# octanis_eps_compact.net
KiCad netlist of a schematic drawn in EAGLE
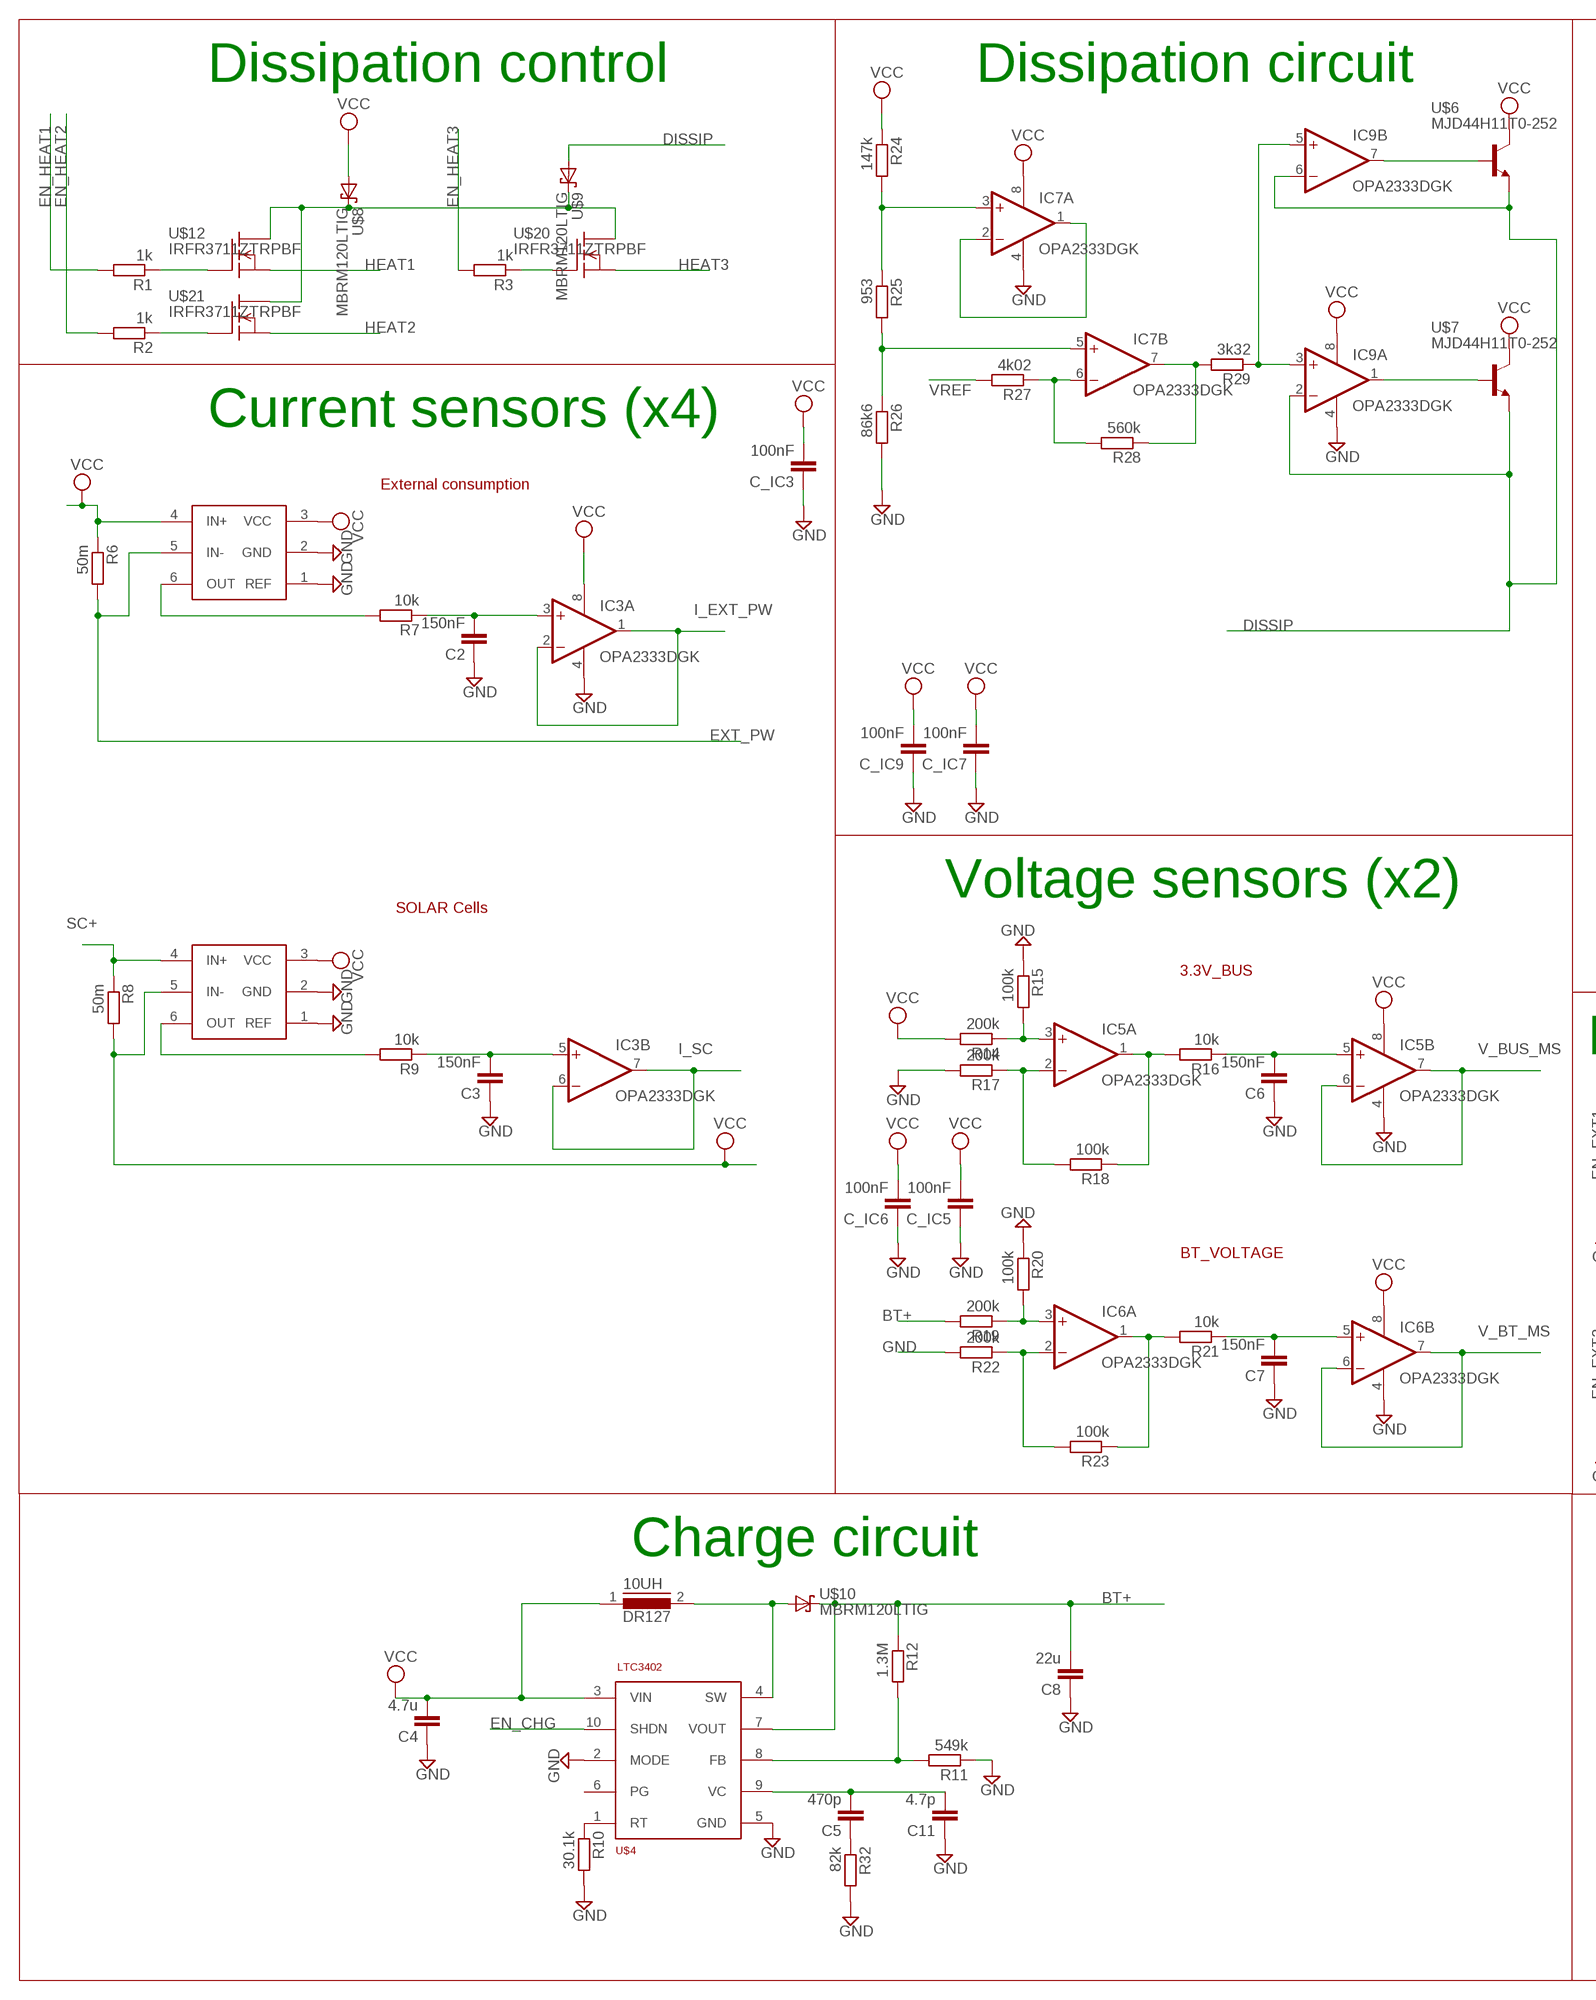
[diagram p0: schematic, sheet 1, part 1 of 2]
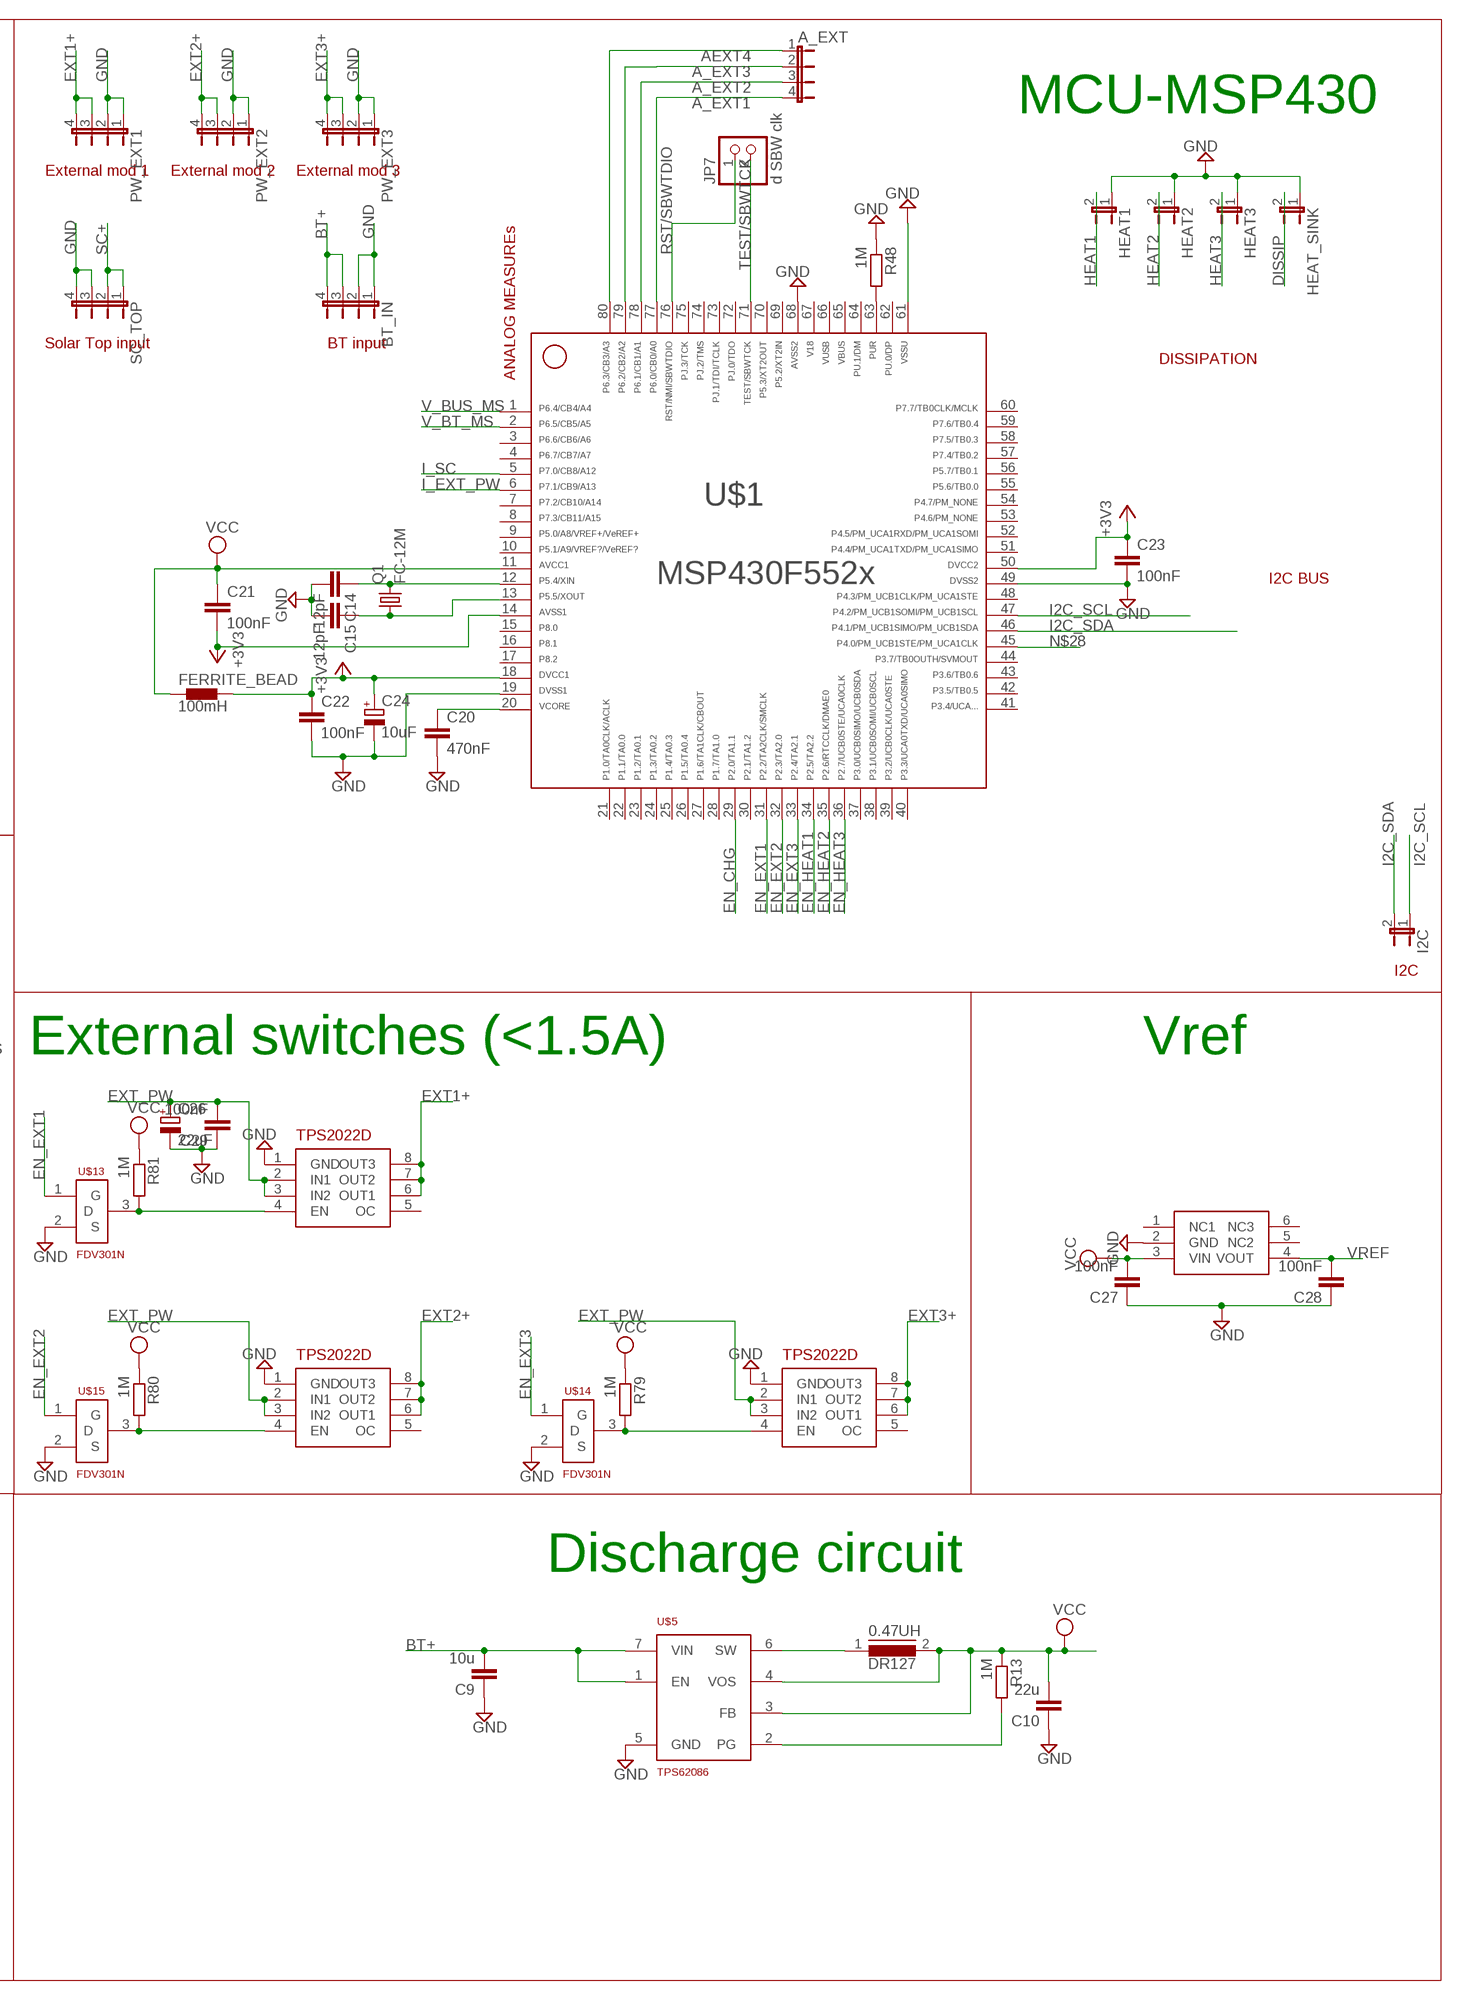
[diagram p1: schematic, sheet 1, part 2 of 2]

(export (version "E")
  (design (tool "Eeschema 10.0.6"))
  (components
    (comp (ref "0.47UH")
      (value "DR127")
      (footprint "eagle-import:DR127")
      (libsource (lib "eagle-import") (part "DR127"))
    )
    (comp (ref "10UH")
      (value "DR127")
      (footprint "eagle-import:DR127")
      (libsource (lib "eagle-import") (part "DR127"))
    )
    (comp (ref "A_EXT")
      (value "JP4E")
      (footprint "eagle-import:JP4")
      (libsource (lib "eagle-import") (part "JP4E"))
    )
    (comp (ref "BT_IN")
      (value "JP4E")
      (footprint "eagle-import:JP4")
      (libsource (lib "eagle-import") (part "JP4E"))
    )
    (comp (ref "C2")
      (value "150nF")
      (footprint "eagle-import:C0603")
      (libsource (lib "eagle-import") (part "C-EUC0603"))
    )
    (comp (ref "C3")
      (value "150nF")
      (footprint "eagle-import:C0603")
      (libsource (lib "eagle-import") (part "C-EUC0603"))
    )
    (comp (ref "C4")
      (value "4.7u")
      (footprint "eagle-import:C0603")
      (libsource (lib "eagle-import") (part "C-EUC0603"))
    )
    (comp (ref "C5")
      (value "470p")
      (footprint "eagle-import:C0603")
      (libsource (lib "eagle-import") (part "C-EUC0603"))
    )
    (comp (ref "C6")
      (value "150nF")
      (footprint "eagle-import:C0603")
      (libsource (lib "eagle-import") (part "C-EUC0603"))
    )
    (comp (ref "C7")
      (value "150nF")
      (footprint "eagle-import:C0603")
      (libsource (lib "eagle-import") (part "C-EUC0603"))
    )
    (comp (ref "C8")
      (value "22u")
      (footprint "eagle-import:C0603")
      (libsource (lib "eagle-import") (part "C-EUC0603"))
    )
    (comp (ref "C9")
      (value "10u")
      (footprint "eagle-import:C0603")
      (libsource (lib "eagle-import") (part "C-EUC0603"))
    )
    (comp (ref "C10")
      (value "22u")
      (footprint "eagle-import:C0603")
      (libsource (lib "eagle-import") (part "C-EUC0603"))
    )
    (comp (ref "C11")
      (value "4.7p")
      (footprint "eagle-import:C0603")
      (libsource (lib "eagle-import") (part "C-EUC0603"))
    )
    (comp (ref "C14")
      (value "12pF")
      (footprint "eagle-import:C0603")
      (libsource (lib "eagle-import") (part "C-EUC0603"))
    )
    (comp (ref "C15")
      (value "12pF")
      (footprint "eagle-import:C0603")
      (libsource (lib "eagle-import") (part "C-EUC0603"))
    )
    (comp (ref "C20")
      (value "470nF")
      (footprint "eagle-import:C0603")
      (libsource (lib "eagle-import") (part "C-EUC0603"))
    )
    (comp (ref "C21")
      (value "100nF")
      (footprint "eagle-import:C0603")
      (libsource (lib "eagle-import") (part "C-EUC0603"))
    )
    (comp (ref "C22")
      (value "100nF")
      (footprint "eagle-import:C0603")
      (libsource (lib "eagle-import") (part "C-EUC0603"))
    )
    (comp (ref "C23")
      (value "100nF")
      (footprint "eagle-import:C0603")
      (libsource (lib "eagle-import") (part "C-EUC0603"))
    )
    (comp (ref "C24")
      (value "10uF")
      (footprint "eagle-import:A_3216-18R")
      (libsource (lib "eagle-import") (part "CPOL-EUA/3216-18R"))
    )
    (comp (ref "C26")
      (value "22uF")
      (footprint "eagle-import:A_3216-18R")
      (libsource (lib "eagle-import") (part "CPOL-EUA/3216-18R"))
    )
    (comp (ref "C27")
      (value "100nF")
      (footprint "eagle-import:C0603")
      (libsource (lib "eagle-import") (part "C-EUC0603"))
    )
    (comp (ref "C28")
      (value "100nF")
      (footprint "eagle-import:C0603")
      (libsource (lib "eagle-import") (part "C-EUC0603"))
    )
    (comp (ref "C29")
      (value "100nF")
      (footprint "eagle-import:C0603")
      (libsource (lib "eagle-import") (part "C-EUC0603"))
    )
    (comp (ref "C_IC3")
      (value "100nF")
      (footprint "eagle-import:C0603")
      (libsource (lib "eagle-import") (part "C-EUC0603"))
    )
    (comp (ref "C_IC5")
      (value "100nF")
      (footprint "eagle-import:C0603")
      (libsource (lib "eagle-import") (part "C-EUC0603"))
    )
    (comp (ref "C_IC6")
      (value "100nF")
      (footprint "eagle-import:C0603")
      (libsource (lib "eagle-import") (part "C-EUC0603"))
    )
    (comp (ref "C_IC7")
      (value "100nF")
      (footprint "eagle-import:C0603")
      (libsource (lib "eagle-import") (part "C-EUC0603"))
    )
    (comp (ref "C_IC9")
      (value "100nF")
      (footprint "eagle-import:C0603")
      (libsource (lib "eagle-import") (part "C-EUC0603"))
    )
    (comp (ref "FERRITE_BEAD")
      (value "100mH")
      (footprint "eagle-import:0402")
      (libsource (lib "eagle-import") (part "BLM15HD601SN1"))
    )
    (comp (ref "HEAT1")
      (value "JP1E")
      (footprint "eagle-import:JP1")
      (libsource (lib "eagle-import") (part "JP1E"))
    )
    (comp (ref "HEAT2")
      (value "JP1E")
      (footprint "eagle-import:JP1")
      (libsource (lib "eagle-import") (part "JP1E"))
    )
    (comp (ref "HEAT3")
      (value "JP1E")
      (footprint "eagle-import:JP1")
      (libsource (lib "eagle-import") (part "JP1E"))
    )
    (comp (ref "HEAT_SINK")
      (value "JP1E")
      (footprint "eagle-import:JP1")
      (libsource (lib "eagle-import") (part "JP1E"))
    )
    (comp (ref "I2C")
      (value "JP1E")
      (footprint "eagle-import:JP1")
      (libsource (lib "eagle-import") (part "JP1E"))
    )
    (comp (ref "IC3")
      (value "OPA2333DGK")
      (footprint "eagle-import:MSOP08")
      (libsource (lib "eagle-import") (part "OPA2333DGK"))
    )
    (comp (ref "IC5")
      (value "OPA2333DGK")
      (footprint "eagle-import:MSOP08")
      (libsource (lib "eagle-import") (part "OPA2333DGK"))
    )
    (comp (ref "IC6")
      (value "OPA2333DGK")
      (footprint "eagle-import:MSOP08")
      (libsource (lib "eagle-import") (part "OPA2333DGK"))
    )
    (comp (ref "IC7")
      (value "OPA2333DGK")
      (footprint "eagle-import:MSOP08")
      (libsource (lib "eagle-import") (part "OPA2333DGK"))
    )
    (comp (ref "IC9")
      (value "OPA2333DGK")
      (footprint "eagle-import:MSOP08")
      (libsource (lib "eagle-import") (part "OPA2333DGK"))
    )
    (comp (ref "JP7")
      (value "d SBW clk")
      (footprint "eagle-import:1X02")
      (libsource (lib "eagle-import") (part "PINHD-1X2"))
    )
    (comp (ref "PW_EXT1")
      (value "JP4E")
      (footprint "eagle-import:JP4")
      (libsource (lib "eagle-import") (part "JP4E"))
    )
    (comp (ref "PW_EXT2")
      (value "JP4E")
      (footprint "eagle-import:JP4")
      (libsource (lib "eagle-import") (part "JP4E"))
    )
    (comp (ref "PW_EXT3")
      (value "JP4E")
      (footprint "eagle-import:JP4")
      (libsource (lib "eagle-import") (part "JP4E"))
    )
    (comp (ref "Q1")
      (value "FC-12M")
      (footprint "eagle-import:FC-12M")
      (libsource (lib "eagle-import") (part "FC-12M"))
    )
    (comp (ref "R1")
      (value "1k")
      (footprint "eagle-import:R0603")
      (libsource (lib "eagle-import") (part "R-EU_R0603"))
    )
    (comp (ref "R2")
      (value "1k")
      (footprint "eagle-import:R0603")
      (libsource (lib "eagle-import") (part "R-EU_R0603"))
    )
    (comp (ref "R3")
      (value "1k")
      (footprint "eagle-import:R0603")
      (libsource (lib "eagle-import") (part "R-EU_R0603"))
    )
    (comp (ref "R6")
      (value "50m")
      (footprint "eagle-import:R1206")
      (libsource (lib "eagle-import") (part "R-EU_R1206"))
    )
    (comp (ref "R7")
      (value "10k")
      (footprint "eagle-import:R0603")
      (libsource (lib "eagle-import") (part "R-EU_R0603"))
    )
    (comp (ref "R8")
      (value "50m")
      (footprint "eagle-import:R1206")
      (libsource (lib "eagle-import") (part "R-EU_R1206"))
    )
    (comp (ref "R9")
      (value "10k")
      (footprint "eagle-import:R0603")
      (libsource (lib "eagle-import") (part "R-EU_R0603"))
    )
    (comp (ref "R10")
      (value "30.1k")
      (footprint "eagle-import:R0603")
      (libsource (lib "eagle-import") (part "R-EU_R0603"))
    )
    (comp (ref "R11")
      (value "549k")
      (footprint "eagle-import:R0603")
      (libsource (lib "eagle-import") (part "R-EU_R0603"))
    )
    (comp (ref "R12")
      (value "1.3M")
      (footprint "eagle-import:R0603")
      (libsource (lib "eagle-import") (part "R-EU_R0603"))
    )
    (comp (ref "R13")
      (value "1M")
      (footprint "eagle-import:R0603")
      (libsource (lib "eagle-import") (part "R-EU_R0603"))
    )
    (comp (ref "R14")
      (value "200k")
      (footprint "eagle-import:R0603")
      (libsource (lib "eagle-import") (part "R-EU_R0603"))
    )
    (comp (ref "R15")
      (value "100k")
      (footprint "eagle-import:R0603")
      (libsource (lib "eagle-import") (part "R-EU_R0603"))
    )
    (comp (ref "R16")
      (value "10k")
      (footprint "eagle-import:R0603")
      (libsource (lib "eagle-import") (part "R-EU_R0603"))
    )
    (comp (ref "R17")
      (value "200k")
      (footprint "eagle-import:R0603")
      (libsource (lib "eagle-import") (part "R-EU_R0603"))
    )
    (comp (ref "R18")
      (value "100k")
      (footprint "eagle-import:R0603")
      (libsource (lib "eagle-import") (part "R-EU_R0603"))
    )
    (comp (ref "R19")
      (value "200k")
      (footprint "eagle-import:R0603")
      (libsource (lib "eagle-import") (part "R-EU_R0603"))
    )
    (comp (ref "R20")
      (value "100k")
      (footprint "eagle-import:R0603")
      (libsource (lib "eagle-import") (part "R-EU_R0603"))
    )
    (comp (ref "R21")
      (value "10k")
      (footprint "eagle-import:R0603")
      (libsource (lib "eagle-import") (part "R-EU_R0603"))
    )
    (comp (ref "R22")
      (value "200k")
      (footprint "eagle-import:R0603")
      (libsource (lib "eagle-import") (part "R-EU_R0603"))
    )
    (comp (ref "R23")
      (value "100k")
      (footprint "eagle-import:R0603")
      (libsource (lib "eagle-import") (part "R-EU_R0603"))
    )
    (comp (ref "R24")
      (value "147k")
      (footprint "eagle-import:R0603")
      (libsource (lib "eagle-import") (part "R-EU_R0603"))
    )
    (comp (ref "R25")
      (value "953")
      (footprint "eagle-import:R0603")
      (libsource (lib "eagle-import") (part "R-EU_R0603"))
    )
    (comp (ref "R26")
      (value "86k6")
      (footprint "eagle-import:R0603")
      (libsource (lib "eagle-import") (part "R-EU_R0603"))
    )
    (comp (ref "R27")
      (value "4k02")
      (footprint "eagle-import:R0603")
      (libsource (lib "eagle-import") (part "R-EU_R0603"))
    )
    (comp (ref "R28")
      (value "560k")
      (footprint "eagle-import:R0603")
      (libsource (lib "eagle-import") (part "R-EU_R0603"))
    )
    (comp (ref "R29")
      (value "3k32")
      (footprint "eagle-import:R0603")
      (libsource (lib "eagle-import") (part "R-EU_R0603"))
    )
    (comp (ref "R32")
      (value "82k")
      (footprint "eagle-import:R0603")
      (libsource (lib "eagle-import") (part "R-EU_R0603"))
    )
    (comp (ref "R48")
      (value "1M")
      (footprint "eagle-import:R0603")
      (libsource (lib "eagle-import") (part "R-EU_R0603"))
    )
    (comp (ref "R79")
      (value "1M")
      (footprint "eagle-import:R0603")
      (libsource (lib "eagle-import") (part "R-EU_R0603"))
    )
    (comp (ref "R80")
      (value "1M")
      (footprint "eagle-import:R0603")
      (libsource (lib "eagle-import") (part "R-EU_R0603"))
    )
    (comp (ref "R81")
      (value "1M")
      (footprint "eagle-import:R0603")
      (libsource (lib "eagle-import") (part "R-EU_R0603"))
    )
    (comp (ref "SC_TOP")
      (value "JP4E")
      (footprint "eagle-import:JP4")
      (libsource (lib "eagle-import") (part "JP4E"))
    )
    (comp (ref "U$1")
      (value "F552X---PN80")
      (footprint "eagle-import:PN80")
      (libsource (lib "eagle-import") (part "F552X---PN80"))
    )
    (comp (ref "U$2")
      (value "INA213")
      (footprint "eagle-import:SC70-6")
      (libsource (lib "eagle-import") (part "INA213"))
    )
    (comp (ref "U$3")
      (value "INA213")
      (footprint "eagle-import:SC70-6")
      (libsource (lib "eagle-import") (part "INA213"))
    )
    (comp (ref "U$4")
      (value "LTC3402")
      (footprint "eagle-import:MSOP10")
      (libsource (lib "eagle-import") (part "LTC3402"))
    )
    (comp (ref "U$5")
      (value "TPS62086")
      (footprint "eagle-import:QFN-7")
      (libsource (lib "eagle-import") (part "TPS62086"))
    )
    (comp (ref "U$6")
      (value "MJD44H11T0-252")
      (footprint "eagle-import:TO252")
      (libsource (lib "eagle-import") (part "MJD44H11T0-252"))
    )
    (comp (ref "U$7")
      (value "MJD44H11T0-252")
      (footprint "eagle-import:TO252")
      (libsource (lib "eagle-import") (part "MJD44H11T0-252"))
    )
    (comp (ref "U$8")
      (value "MBRM120LTIG")
      (footprint "eagle-import:DO216AA")
      (libsource (lib "eagle-import") (part "MBRM120LTIG"))
    )
    (comp (ref "U$9")
      (value "MBRM120LTIG")
      (footprint "eagle-import:DO216AA")
      (libsource (lib "eagle-import") (part "MBRM120LTIG"))
    )
    (comp (ref "U$10")
      (value "MBRM120LTIG")
      (footprint "eagle-import:DO216AA")
      (libsource (lib "eagle-import") (part "MBRM120LTIG"))
    )
    (comp (ref "U$12")
      (value "IRFR3711ZTRPBF")
      (footprint "eagle-import:TO252")
      (libsource (lib "eagle-import") (part "IRFR3711ZTRPBF"))
    )
    (comp (ref "U$13")
      (value "FDV301N")
      (footprint "eagle-import:SOT23")
      (libsource (lib "eagle-import") (part "FDV301N"))
    )
    (comp (ref "U$14")
      (value "FDV301N")
      (footprint "eagle-import:SOT23")
      (libsource (lib "eagle-import") (part "FDV301N"))
    )
    (comp (ref "U$15")
      (value "FDV301N")
      (footprint "eagle-import:SOT23")
      (libsource (lib "eagle-import") (part "FDV301N"))
    )
    (comp (ref "U$16")
      (value "TPS2022D")
      (footprint "eagle-import:SO8")
      (libsource (lib "eagle-import") (part "TPS2022D"))
    )
    (comp (ref "U$17")
      (value "TPS2022D")
      (footprint "eagle-import:SO8")
      (libsource (lib "eagle-import") (part "TPS2022D"))
    )
    (comp (ref "U$18")
      (value "TPS2022D")
      (footprint "eagle-import:SO8")
      (libsource (lib "eagle-import") (part "TPS2022D"))
    )
    (comp (ref "U$19")
      (value "ADR127B")
      (footprint "eagle-import:TSOT23-6")
      (libsource (lib "eagle-import") (part "ADR127B"))
    )
    (comp (ref "U$20")
      (value "IRFR3711ZTRPBF")
      (footprint "eagle-import:TO252")
      (libsource (lib "eagle-import") (part "IRFR3711ZTRPBF"))
    )
    (comp (ref "U$21")
      (value "IRFR3711ZTRPBF")
      (footprint "eagle-import:TO252")
      (libsource (lib "eagle-import") (part "IRFR3711ZTRPBF"))
    )
  )
  (nets
    (net (code "1") (name "+3V3") (class "Default")
      (node (ref "C21") (pin "2") (pinfunction "2_2") (pintype "passive"))
      (node (ref "C22") (pin "1") (pinfunction "1_1") (pintype "passive"))
      (node (ref "C23") (pin "1") (pinfunction "1_1") (pintype "passive"))
      (node (ref "C24") (pin "+") (pinfunction "+_+") (pintype "passive"))
      (node (ref "FERRITE_BEAD") (pin "2") (pinfunction "2_2") (pintype "passive"))
      (node (ref "U$1") (pin "14") (pinfunction "14_14") (pintype "power_in"))
      (node (ref "U$1") (pin "18") (pinfunction "18_18") (pintype "power_in"))
      (node (ref "U$1") (pin "50") (pinfunction "50_50") (pintype "power_in"))
    )
    (net (code "2") (name "/65") (class "Default")
      (node (ref "U$1") (pin "65") (pinfunction "65_65") (pintype "power_in"))
    )
    (net (code "3") (name "/66") (class "Default")
      (node (ref "U$1") (pin "66") (pinfunction "66_66") (pintype "power_in"))
    )
    (net (code "4") (name "/67") (class "Default")
      (node (ref "U$1") (pin "67") (pinfunction "67_67") (pintype "power_in"))
    )
    (net (code "5") (name "/AEXT4") (class "Default")
      (node (ref "A_EXT") (pin "1") (pinfunction "1_1") (pintype "passive"))
      (node (ref "U$1") (pin "80") (pinfunction "80_80") (pintype "bidirectional"))
    )
    (net (code "6") (name "/A_EXT1") (class "Default")
      (node (ref "A_EXT") (pin "4") (pinfunction "4_4") (pintype "passive"))
      (node (ref "U$1") (pin "77") (pinfunction "77_77") (pintype "bidirectional"))
    )
    (net (code "7") (name "/A_EXT2") (class "Default")
      (node (ref "A_EXT") (pin "3") (pinfunction "3_3") (pintype "passive"))
      (node (ref "U$1") (pin "78") (pinfunction "78_78") (pintype "bidirectional"))
    )
    (net (code "8") (name "/A_EXT3") (class "Default")
      (node (ref "A_EXT") (pin "2") (pinfunction "2_2") (pintype "passive"))
      (node (ref "U$1") (pin "79") (pinfunction "79_79") (pintype "bidirectional"))
    )
    (net (code "9") (name "/BT+") (class "Default")
      (node (ref "BT_IN") (pin "3") (pinfunction "3_3") (pintype "passive"))
      (node (ref "BT_IN") (pin "4") (pinfunction "4_4") (pintype "passive"))
      (node (ref "C8") (pin "2") (pinfunction "2_2") (pintype "passive"))
      (node (ref "C9") (pin "2") (pinfunction "2_2") (pintype "passive"))
      (node (ref "R12") (pin "1") (pinfunction "1_1") (pintype "passive"))
      (node (ref "R19") (pin "2") (pinfunction "2_2") (pintype "passive"))
      (node (ref "U$10") (pin "C") (pinfunction "K_C") (pintype "passive"))
      (node (ref "U$4") (pin "7") (pinfunction "VOUT_7") (pintype "bidirectional"))
      (node (ref "U$5") (pin "1") (pinfunction "EN_1") (pintype "bidirectional"))
      (node (ref "U$5") (pin "7") (pinfunction "VIN_7") (pintype "bidirectional"))
    )
    (net (code "10") (name "/DISSIP") (class "Default")
      (node (ref "HEAT_SINK") (pin "2") (pinfunction "2_2") (pintype "passive"))
      (node (ref "IC9") (pin "2") (pinfunction "-IN_2") (pintype "input"))
      (node (ref "IC9") (pin "6") (pinfunction "-IN_6") (pintype "input"))
      (node (ref "U$12") (pin "2") (pinfunction "D_2") (pintype "passive"))
      (node (ref "U$20") (pin "2") (pinfunction "D_2") (pintype "passive"))
      (node (ref "U$21") (pin "2") (pinfunction "D_2") (pintype "passive"))
      (node (ref "U$6") (pin "3") (pinfunction "E_3") (pintype "passive"))
      (node (ref "U$7") (pin "3") (pinfunction "E_3") (pintype "passive"))
      (node (ref "U$8") (pin "C") (pinfunction "K_C") (pintype "passive"))
      (node (ref "U$9") (pin "A") (pinfunction "A_A") (pintype "passive"))
      (node (ref "U$9") (pin "C") (pinfunction "K_C") (pintype "passive"))
    )
    (net (code "11") (name "/EN_CHG") (class "Default")
      (node (ref "U$1") (pin "29") (pinfunction "29_29") (pintype "bidirectional"))
      (node (ref "U$4") (pin "10") (pinfunction "SHDN_10") (pintype "bidirectional"))
    )
    (net (code "12") (name "/EN_EXT1") (class "Default")
      (node (ref "U$1") (pin "31") (pinfunction "31_31") (pintype "bidirectional"))
      (node (ref "U$13") (pin "1") (pinfunction "G_1") (pintype "bidirectional"))
    )
    (net (code "13") (name "/EN_EXT2") (class "Default")
      (node (ref "U$1") (pin "32") (pinfunction "32_32") (pintype "bidirectional"))
      (node (ref "U$15") (pin "1") (pinfunction "G_1") (pintype "bidirectional"))
    )
    (net (code "14") (name "/EN_EXT3") (class "Default")
      (node (ref "U$1") (pin "33") (pinfunction "33_33") (pintype "bidirectional"))
      (node (ref "U$14") (pin "1") (pinfunction "G_1") (pintype "bidirectional"))
    )
    (net (code "15") (name "/EN_HEAT1") (class "Default")
      (node (ref "R1") (pin "2") (pinfunction "2_2") (pintype "passive"))
      (node (ref "U$1") (pin "34") (pinfunction "34_34") (pintype "bidirectional"))
    )
    (net (code "16") (name "/EN_HEAT2") (class "Default")
      (node (ref "R2") (pin "2") (pinfunction "2_2") (pintype "passive"))
      (node (ref "U$1") (pin "35") (pinfunction "35_35") (pintype "bidirectional"))
    )
    (net (code "17") (name "/EN_HEAT3") (class "Default")
      (node (ref "R3") (pin "2") (pinfunction "2_2") (pintype "passive"))
      (node (ref "U$1") (pin "36") (pinfunction "36_36") (pintype "bidirectional"))
    )
    (net (code "18") (name "/EXT1+") (class "Default")
      (node (ref "PW_EXT1") (pin "3") (pinfunction "3_3") (pintype "passive"))
      (node (ref "PW_EXT1") (pin "4") (pinfunction "4_4") (pintype "passive"))
      (node (ref "U$16") (pin "6") (pinfunction "OUT1_6") (pintype "bidirectional"))
      (node (ref "U$16") (pin "7") (pinfunction "OUT2_7") (pintype "bidirectional"))
      (node (ref "U$16") (pin "8") (pinfunction "OUT3_8") (pintype "bidirectional"))
    )
    (net (code "19") (name "/EXT2+") (class "Default")
      (node (ref "PW_EXT2") (pin "3") (pinfunction "3_3") (pintype "passive"))
      (node (ref "PW_EXT2") (pin "4") (pinfunction "4_4") (pintype "passive"))
      (node (ref "U$17") (pin "6") (pinfunction "OUT1_6") (pintype "bidirectional"))
      (node (ref "U$17") (pin "7") (pinfunction "OUT2_7") (pintype "bidirectional"))
      (node (ref "U$17") (pin "8") (pinfunction "OUT3_8") (pintype "bidirectional"))
    )
    (net (code "20") (name "/EXT3+") (class "Default")
      (node (ref "PW_EXT3") (pin "3") (pinfunction "3_3") (pintype "passive"))
      (node (ref "PW_EXT3") (pin "4") (pinfunction "4_4") (pintype "passive"))
      (node (ref "U$18") (pin "6") (pinfunction "OUT1_6") (pintype "bidirectional"))
      (node (ref "U$18") (pin "7") (pinfunction "OUT2_7") (pintype "bidirectional"))
      (node (ref "U$18") (pin "8") (pinfunction "OUT3_8") (pintype "bidirectional"))
    )
    (net (code "21") (name "/EXT_PW") (class "Default")
      (node (ref "C26") (pin "+") (pinfunction "+_+") (pintype "passive"))
      (node (ref "C29") (pin "2") (pinfunction "2_2") (pintype "passive"))
      (node (ref "R6") (pin "2") (pinfunction "2_2") (pintype "passive"))
      (node (ref "U$16") (pin "2") (pinfunction "IN1_2") (pintype "bidirectional"))
      (node (ref "U$16") (pin "3") (pinfunction "IN2_3") (pintype "bidirectional"))
      (node (ref "U$17") (pin "2") (pinfunction "IN1_2") (pintype "bidirectional"))
      (node (ref "U$17") (pin "3") (pinfunction "IN2_3") (pintype "bidirectional"))
      (node (ref "U$18") (pin "2") (pinfunction "IN1_2") (pintype "bidirectional"))
      (node (ref "U$18") (pin "3") (pinfunction "IN2_3") (pintype "bidirectional"))
      (node (ref "U$2") (pin "5") (pinfunction "IN-_5") (pintype "bidirectional"))
    )
    (net (code "22") (name "/HEAT1") (class "Default")
      (node (ref "HEAT1") (pin "2") (pinfunction "2_2") (pintype "passive"))
      (node (ref "U$12") (pin "3") (pinfunction "S_3") (pintype "passive"))
    )
    (net (code "23") (name "/HEAT2") (class "Default")
      (node (ref "HEAT2") (pin "2") (pinfunction "2_2") (pintype "passive"))
      (node (ref "U$21") (pin "3") (pinfunction "S_3") (pintype "passive"))
    )
    (net (code "24") (name "/HEAT3") (class "Default")
      (node (ref "HEAT3") (pin "2") (pinfunction "2_2") (pintype "passive"))
      (node (ref "U$20") (pin "3") (pinfunction "S_3") (pintype "passive"))
    )
    (net (code "25") (name "/I2C_SCL") (class "Default")
      (node (ref "I2C") (pin "1") (pinfunction "1_1") (pintype "passive"))
      (node (ref "U$1") (pin "47") (pinfunction "47_47") (pintype "bidirectional"))
    )
    (net (code "26") (name "/I2C_SDA") (class "Default")
      (node (ref "I2C") (pin "2") (pinfunction "2_2") (pintype "passive"))
      (node (ref "U$1") (pin "46") (pinfunction "46_46") (pintype "bidirectional"))
    )
    (net (code "27") (name "/I_EXT_PW") (class "Default")
      (node (ref "IC3") (pin "1") (pinfunction "OUT_1") (pintype "output"))
      (node (ref "IC3") (pin "2") (pinfunction "-IN_2") (pintype "input"))
      (node (ref "U$1") (pin "6") (pinfunction "6_6") (pintype "bidirectional"))
    )
    (net (code "28") (name "/I_SC") (class "Default")
      (node (ref "IC3") (pin "6") (pinfunction "-IN_6") (pintype "input"))
      (node (ref "IC3") (pin "7") (pinfunction "OUT_7") (pintype "output"))
      (node (ref "U$1") (pin "5") (pinfunction "5_5") (pintype "bidirectional"))
    )
    (net (code "29") (name "/N$28") (class "Default")
      (node (ref "U$1") (pin "45") (pinfunction "45_45") (pintype "bidirectional"))
    )
    (net (code "30") (name "/RST{slash}SBWTDIO") (class "Default")
      (node (ref "JP7") (pin "1") (pinfunction "1_1") (pintype "passive"))
      (node (ref "U$1") (pin "76") (pinfunction "76_76") (pintype "bidirectional"))
    )
    (net (code "31") (name "/SC+") (class "Default")
      (node (ref "R8") (pin "1") (pinfunction "1_1") (pintype "passive"))
      (node (ref "SC_TOP") (pin "1") (pinfunction "1_1") (pintype "passive"))
      (node (ref "SC_TOP") (pin "2") (pinfunction "2_2") (pintype "passive"))
      (node (ref "U$3") (pin "4") (pinfunction "IN+_4") (pintype "bidirectional"))
    )
    (net (code "32") (name "/TEST{slash}SBWTCK") (class "Default")
      (node (ref "JP7") (pin "2") (pinfunction "2_2") (pintype "passive"))
      (node (ref "U$1") (pin "71") (pinfunction "71_71") (pintype "input"))
    )
    (net (code "33") (name "/VREF") (class "Default")
      (node (ref "C28") (pin "2") (pinfunction "2_2") (pintype "passive"))
      (node (ref "R27") (pin "2") (pinfunction "2_2") (pintype "passive"))
      (node (ref "U$19") (pin "4") (pinfunction "VOUT_4") (pintype "bidirectional"))
    )
    (net (code "34") (name "/V_BT_MS") (class "Default")
      (node (ref "IC6") (pin "6") (pinfunction "-IN_6") (pintype "input"))
      (node (ref "IC6") (pin "7") (pinfunction "OUT_7") (pintype "output"))
      (node (ref "U$1") (pin "2") (pinfunction "2_2") (pintype "bidirectional"))
    )
    (net (code "35") (name "/V_BUS_MS") (class "Default")
      (node (ref "IC5") (pin "6") (pinfunction "-IN_6") (pintype "input"))
      (node (ref "IC5") (pin "7") (pinfunction "OUT_7") (pintype "output"))
      (node (ref "U$1") (pin "1") (pinfunction "1_1") (pintype "bidirectional"))
    )
    (net (code "36") (name "GND") (class "Default")
      (node (ref "BT_IN") (pin "1") (pinfunction "1_1") (pintype "passive"))
      (node (ref "BT_IN") (pin "2") (pinfunction "2_2") (pintype "passive"))
      (node (ref "C10") (pin "1") (pinfunction "1_1") (pintype "passive"))
      (node (ref "C11") (pin "1") (pinfunction "1_1") (pintype "passive"))
      (node (ref "C14") (pin "2") (pinfunction "2_2") (pintype "passive"))
      (node (ref "C15") (pin "2") (pinfunction "2_2") (pintype "passive"))
      (node (ref "C2") (pin "1") (pinfunction "1_1") (pintype "passive"))
      (node (ref "C20") (pin "2") (pinfunction "2_2") (pintype "passive"))
      (node (ref "C22") (pin "2") (pinfunction "2_2") (pintype "passive"))
      (node (ref "C23") (pin "2") (pinfunction "2_2") (pintype "passive"))
      (node (ref "C24") (pin "-") (pinfunction "-_-") (pintype "passive"))
      (node (ref "C26") (pin "-") (pinfunction "-_-") (pintype "passive"))
      (node (ref "C27") (pin "1") (pinfunction "1_1") (pintype "passive"))
      (node (ref "C28") (pin "1") (pinfunction "1_1") (pintype "passive"))
      (node (ref "C29") (pin "1") (pinfunction "1_1") (pintype "passive"))
      (node (ref "C3") (pin "1") (pinfunction "1_1") (pintype "passive"))
      (node (ref "C4") (pin "1") (pinfunction "1_1") (pintype "passive"))
      (node (ref "C6") (pin "1") (pinfunction "1_1") (pintype "passive"))
      (node (ref "C7") (pin "1") (pinfunction "1_1") (pintype "passive"))
      (node (ref "C8") (pin "1") (pinfunction "1_1") (pintype "passive"))
      (node (ref "C9") (pin "1") (pinfunction "1_1") (pintype "passive"))
      (node (ref "C_IC3") (pin "1") (pinfunction "1_1") (pintype "passive"))
      (node (ref "C_IC5") (pin "1") (pinfunction "1_1") (pintype "passive"))
      (node (ref "C_IC6") (pin "1") (pinfunction "1_1") (pintype "passive"))
      (node (ref "C_IC7") (pin "1") (pinfunction "1_1") (pintype "passive"))
      (node (ref "C_IC9") (pin "1") (pinfunction "1_1") (pintype "passive"))
      (node (ref "HEAT1") (pin "1") (pinfunction "1_1") (pintype "passive"))
      (node (ref "HEAT2") (pin "1") (pinfunction "1_1") (pintype "passive"))
      (node (ref "HEAT3") (pin "1") (pinfunction "1_1") (pintype "passive"))
      (node (ref "HEAT_SINK") (pin "1") (pinfunction "1_1") (pintype "passive"))
      (node (ref "IC3") (pin "4") (pinfunction "V-_4") (pintype "power_in"))
      (node (ref "IC5") (pin "4") (pinfunction "V-_4") (pintype "power_in"))
      (node (ref "IC6") (pin "4") (pinfunction "V-_4") (pintype "power_in"))
      (node (ref "IC7") (pin "4") (pinfunction "V-_4") (pintype "power_in"))
      (node (ref "IC9") (pin "4") (pinfunction "V-_4") (pintype "power_in"))
      (node (ref "PW_EXT1") (pin "1") (pinfunction "1_1") (pintype "passive"))
      (node (ref "PW_EXT1") (pin "2") (pinfunction "2_2") (pintype "passive"))
      (node (ref "PW_EXT2") (pin "1") (pinfunction "1_1") (pintype "passive"))
      (node (ref "PW_EXT2") (pin "2") (pinfunction "2_2") (pintype "passive"))
      (node (ref "PW_EXT3") (pin "1") (pinfunction "1_1") (pintype "passive"))
      (node (ref "PW_EXT3") (pin "2") (pinfunction "2_2") (pintype "passive"))
      (node (ref "R10") (pin "2") (pinfunction "2_2") (pintype "passive"))
      (node (ref "R11") (pin "1") (pinfunction "1_1") (pintype "passive"))
      (node (ref "R15") (pin "1") (pinfunction "1_1") (pintype "passive"))
      (node (ref "R17") (pin "2") (pinfunction "2_2") (pintype "passive"))
      (node (ref "R20") (pin "1") (pinfunction "1_1") (pintype "passive"))
      (node (ref "R22") (pin "2") (pinfunction "2_2") (pintype "passive"))
      (node (ref "R26") (pin "2") (pinfunction "2_2") (pintype "passive"))
      (node (ref "R32") (pin "2") (pinfunction "2_2") (pintype "passive"))
      (node (ref "R48") (pin "1") (pinfunction "1_1") (pintype "passive"))
      (node (ref "SC_TOP") (pin "3") (pinfunction "3_3") (pintype "passive"))
      (node (ref "SC_TOP") (pin "4") (pinfunction "4_4") (pintype "passive"))
      (node (ref "U$1") (pin "19") (pinfunction "19_19") (pintype "power_in"))
      (node (ref "U$1") (pin "49") (pinfunction "49_49") (pintype "power_in"))
      (node (ref "U$1") (pin "61") (pinfunction "61_61") (pintype "power_in"))
      (node (ref "U$1") (pin "68") (pinfunction "68_68") (pintype "power_in"))
      (node (ref "U$13") (pin "2") (pinfunction "S_2") (pintype "bidirectional"))
      (node (ref "U$14") (pin "2") (pinfunction "S_2") (pintype "bidirectional"))
      (node (ref "U$15") (pin "2") (pinfunction "S_2") (pintype "bidirectional"))
      (node (ref "U$16") (pin "1") (pinfunction "GND_1") (pintype "bidirectional"))
      (node (ref "U$17") (pin "1") (pinfunction "GND_1") (pintype "bidirectional"))
      (node (ref "U$18") (pin "1") (pinfunction "GND_1") (pintype "bidirectional"))
      (node (ref "U$19") (pin "2") (pinfunction "GND_2") (pintype "bidirectional"))
      (node (ref "U$2") (pin "1") (pinfunction "REF_1") (pintype "bidirectional"))
      (node (ref "U$2") (pin "2") (pinfunction "GND_2") (pintype "bidirectional"))
      (node (ref "U$3") (pin "1") (pinfunction "REF_1") (pintype "bidirectional"))
      (node (ref "U$3") (pin "2") (pinfunction "GND_2") (pintype "bidirectional"))
      (node (ref "U$4") (pin "2") (pinfunction "MODE_2") (pintype "bidirectional"))
      (node (ref "U$4") (pin "5") (pinfunction "GND_5") (pintype "bidirectional"))
      (node (ref "U$5") (pin "5") (pinfunction "GND_5") (pintype "bidirectional"))
    )
    (net (code "37") (name "Net-(C5-Pad1)") (class "Default")
      (node (ref "C5") (pin "1") (pinfunction "1_1") (pintype "passive"))
      (node (ref "R32") (pin "1") (pinfunction "1_1") (pintype "passive"))
    )
    (net (code "38") (name "Net-(C14-Pad1)") (class "Default")
      (node (ref "C14") (pin "1") (pinfunction "1_1") (pintype "passive"))
      (node (ref "Q1") (pin "2") (pinfunction "2_2") (pintype "passive"))
      (node (ref "U$1") (pin "12") (pinfunction "12_12") (pintype "bidirectional"))
    )
    (net (code "39") (name "Net-(C15-Pad1)") (class "Default")
      (node (ref "C15") (pin "1") (pinfunction "1_1") (pintype "passive"))
      (node (ref "Q1") (pin "1") (pinfunction "1_1") (pintype "passive"))
      (node (ref "U$1") (pin "13") (pinfunction "13_13") (pintype "bidirectional"))
    )
    (net (code "40") (name "Net-(C20-Pad1)") (class "Default")
      (node (ref "C20") (pin "1") (pinfunction "1_1") (pintype "passive"))
      (node (ref "U$1") (pin "20") (pinfunction "20_20") (pintype "power_in"))
    )
    (net (code "41") (name "Net-(IC3A-+IN)") (class "Default")
      (node (ref "C2") (pin "2") (pinfunction "2_2") (pintype "passive"))
      (node (ref "IC3") (pin "3") (pinfunction "+IN_3") (pintype "input"))
      (node (ref "R7") (pin "1") (pinfunction "1_1") (pintype "passive"))
    )
    (net (code "42") (name "Net-(IC3B-+IN)") (class "Default")
      (node (ref "C3") (pin "2") (pinfunction "2_2") (pintype "passive"))
      (node (ref "IC3") (pin "5") (pinfunction "+IN_5") (pintype "input"))
      (node (ref "R9") (pin "1") (pinfunction "1_1") (pintype "passive"))
    )
    (net (code "43") (name "Net-(IC5A-+IN)") (class "Default")
      (node (ref "IC5") (pin "3") (pinfunction "+IN_3") (pintype "input"))
      (node (ref "R14") (pin "1") (pinfunction "1_1") (pintype "passive"))
      (node (ref "R15") (pin "2") (pinfunction "2_2") (pintype "passive"))
    )
    (net (code "44") (name "Net-(IC5A--IN)") (class "Default")
      (node (ref "IC5") (pin "2") (pinfunction "-IN_2") (pintype "input"))
      (node (ref "R17") (pin "1") (pinfunction "1_1") (pintype "passive"))
      (node (ref "R18") (pin "2") (pinfunction "2_2") (pintype "passive"))
    )
    (net (code "45") (name "Net-(IC5A-OUT)") (class "Default")
      (node (ref "IC5") (pin "1") (pinfunction "OUT_1") (pintype "output"))
      (node (ref "R16") (pin "2") (pinfunction "2_2") (pintype "passive"))
      (node (ref "R18") (pin "1") (pinfunction "1_1") (pintype "passive"))
    )
    (net (code "46") (name "Net-(IC5B-+IN)") (class "Default")
      (node (ref "C6") (pin "2") (pinfunction "2_2") (pintype "passive"))
      (node (ref "IC5") (pin "5") (pinfunction "+IN_5") (pintype "input"))
      (node (ref "R16") (pin "1") (pinfunction "1_1") (pintype "passive"))
    )
    (net (code "47") (name "Net-(IC6A-+IN)") (class "Default")
      (node (ref "IC6") (pin "3") (pinfunction "+IN_3") (pintype "input"))
      (node (ref "R19") (pin "1") (pinfunction "1_1") (pintype "passive"))
      (node (ref "R20") (pin "2") (pinfunction "2_2") (pintype "passive"))
    )
    (net (code "48") (name "Net-(IC6A--IN)") (class "Default")
      (node (ref "IC6") (pin "2") (pinfunction "-IN_2") (pintype "input"))
      (node (ref "R22") (pin "1") (pinfunction "1_1") (pintype "passive"))
      (node (ref "R23") (pin "2") (pinfunction "2_2") (pintype "passive"))
    )
    (net (code "49") (name "Net-(IC6A-OUT)") (class "Default")
      (node (ref "IC6") (pin "1") (pinfunction "OUT_1") (pintype "output"))
      (node (ref "R21") (pin "2") (pinfunction "2_2") (pintype "passive"))
      (node (ref "R23") (pin "1") (pinfunction "1_1") (pintype "passive"))
    )
    (net (code "50") (name "Net-(IC6B-+IN)") (class "Default")
      (node (ref "C7") (pin "2") (pinfunction "2_2") (pintype "passive"))
      (node (ref "IC6") (pin "5") (pinfunction "+IN_5") (pintype "input"))
      (node (ref "R21") (pin "1") (pinfunction "1_1") (pintype "passive"))
    )
    (net (code "51") (name "Net-(IC7A-+IN)") (class "Default")
      (node (ref "IC7") (pin "3") (pinfunction "+IN_3") (pintype "input"))
      (node (ref "R24") (pin "2") (pinfunction "2_2") (pintype "passive"))
      (node (ref "R25") (pin "1") (pinfunction "1_1") (pintype "passive"))
    )
    (net (code "52") (name "Net-(IC7A--IN)") (class "Default")
      (node (ref "IC7") (pin "1") (pinfunction "OUT_1") (pintype "output"))
      (node (ref "IC7") (pin "2") (pinfunction "-IN_2") (pintype "input"))
    )
    (net (code "53") (name "Net-(IC7B-+IN)") (class "Default")
      (node (ref "IC7") (pin "5") (pinfunction "+IN_5") (pintype "input"))
      (node (ref "R25") (pin "2") (pinfunction "2_2") (pintype "passive"))
      (node (ref "R26") (pin "1") (pinfunction "1_1") (pintype "passive"))
    )
    (net (code "54") (name "Net-(IC7B--IN)") (class "Default")
      (node (ref "IC7") (pin "6") (pinfunction "-IN_6") (pintype "input"))
      (node (ref "R27") (pin "1") (pinfunction "1_1") (pintype "passive"))
      (node (ref "R28") (pin "2") (pinfunction "2_2") (pintype "passive"))
    )
    (net (code "55") (name "Net-(IC7B-OUT)") (class "Default")
      (node (ref "IC7") (pin "7") (pinfunction "OUT_7") (pintype "output"))
      (node (ref "R28") (pin "1") (pinfunction "1_1") (pintype "passive"))
      (node (ref "R29") (pin "2") (pinfunction "2_2") (pintype "passive"))
    )
    (net (code "56") (name "Net-(IC9A-+IN)") (class "Default")
      (node (ref "IC9") (pin "3") (pinfunction "+IN_3") (pintype "input"))
      (node (ref "IC9") (pin "5") (pinfunction "+IN_5") (pintype "input"))
      (node (ref "R29") (pin "1") (pinfunction "1_1") (pintype "passive"))
    )
    (net (code "57") (name "Net-(IC9A-OUT)") (class "Default")
      (node (ref "IC9") (pin "1") (pinfunction "OUT_1") (pintype "output"))
      (node (ref "U$7") (pin "1") (pinfunction "B_1") (pintype "passive"))
    )
    (net (code "58") (name "Net-(IC9B-OUT)") (class "Default")
      (node (ref "IC9") (pin "7") (pinfunction "OUT_7") (pintype "output"))
      (node (ref "U$6") (pin "1") (pinfunction "B_1") (pintype "passive"))
    )
    (net (code "59") (name "Net-(R48-Pad2)") (class "Default")
      (node (ref "R48") (pin "2") (pinfunction "2_2") (pintype "passive"))
      (node (ref "U$1") (pin "63") (pinfunction "63_63") (pintype "bidirectional"))
    )
    (net (code "60") (name "Net-(U$2-OUT)") (class "Default")
      (node (ref "R7") (pin "2") (pinfunction "2_2") (pintype "passive"))
      (node (ref "U$2") (pin "6") (pinfunction "OUT_6") (pintype "bidirectional"))
    )
    (net (code "61") (name "Net-(U$3-OUT)") (class "Default")
      (node (ref "R9") (pin "2") (pinfunction "2_2") (pintype "passive"))
      (node (ref "U$3") (pin "6") (pinfunction "OUT_6") (pintype "bidirectional"))
    )
    (net (code "62") (name "Net-(U$4-FB)") (class "Default")
      (node (ref "R11") (pin "2") (pinfunction "2_2") (pintype "passive"))
      (node (ref "R12") (pin "2") (pinfunction "2_2") (pintype "passive"))
      (node (ref "U$4") (pin "8") (pinfunction "FB_8") (pintype "bidirectional"))
    )
    (net (code "63") (name "Net-(U$4-RT)") (class "Default")
      (node (ref "R10") (pin "1") (pinfunction "1_1") (pintype "passive"))
      (node (ref "U$4") (pin "1") (pinfunction "RT_1") (pintype "bidirectional"))
    )
    (net (code "64") (name "Net-(U$4-SW)") (class "Default")
      (node (ref "10UH") (pin "2") (pinfunction "2_2") (pintype "passive"))
      (node (ref "U$10") (pin "A") (pinfunction "A_A") (pintype "passive"))
      (node (ref "U$4") (pin "4") (pinfunction "SW_4") (pintype "bidirectional"))
    )
    (net (code "65") (name "Net-(U$4-VC)") (class "Default")
      (node (ref "C11") (pin "2") (pinfunction "2_2") (pintype "passive"))
      (node (ref "C5") (pin "2") (pinfunction "2_2") (pintype "passive"))
      (node (ref "U$4") (pin "9") (pinfunction "VC_9") (pintype "bidirectional"))
    )
    (net (code "66") (name "Net-(U$5-PG)") (class "Default")
      (node (ref "R13") (pin "2") (pinfunction "2_2") (pintype "passive"))
      (node (ref "U$5") (pin "2") (pinfunction "PG_2") (pintype "bidirectional"))
    )
    (net (code "67") (name "Net-(U$5-SW)") (class "Default")
      (node (ref "0.47UH") (pin "1") (pinfunction "1_1") (pintype "passive"))
      (node (ref "U$5") (pin "6") (pinfunction "SW_6") (pintype "bidirectional"))
    )
    (net (code "68") (name "Net-(U$12-G)") (class "Default")
      (node (ref "R1") (pin "1") (pinfunction "1_1") (pintype "passive"))
      (node (ref "U$12") (pin "1") (pinfunction "G_1") (pintype "passive"))
    )
    (net (code "69") (name "Net-(U$13-D)") (class "Default")
      (node (ref "R81") (pin "2") (pinfunction "2_2") (pintype "passive"))
      (node (ref "U$13") (pin "3") (pinfunction "D_3") (pintype "bidirectional"))
      (node (ref "U$16") (pin "4") (pinfunction "EN_4") (pintype "bidirectional"))
    )
    (net (code "70") (name "Net-(U$14-D)") (class "Default")
      (node (ref "R79") (pin "2") (pinfunction "2_2") (pintype "passive"))
      (node (ref "U$14") (pin "3") (pinfunction "D_3") (pintype "bidirectional"))
      (node (ref "U$18") (pin "4") (pinfunction "EN_4") (pintype "bidirectional"))
    )
    (net (code "71") (name "Net-(U$15-D)") (class "Default")
      (node (ref "R80") (pin "2") (pinfunction "2_2") (pintype "passive"))
      (node (ref "U$15") (pin "3") (pinfunction "D_3") (pintype "bidirectional"))
      (node (ref "U$17") (pin "4") (pinfunction "EN_4") (pintype "bidirectional"))
    )
    (net (code "72") (name "Net-(U$20-G)") (class "Default")
      (node (ref "R3") (pin "1") (pinfunction "1_1") (pintype "passive"))
      (node (ref "U$20") (pin "1") (pinfunction "G_1") (pintype "passive"))
    )
    (net (code "73") (name "Net-(U$21-G)") (class "Default")
      (node (ref "R2") (pin "1") (pinfunction "1_1") (pintype "passive"))
      (node (ref "U$21") (pin "1") (pinfunction "G_1") (pintype "passive"))
    )
    (net (code "74") (name "VCC") (class "Default")
      (node (ref "0.47UH") (pin "2") (pinfunction "2_2") (pintype "passive"))
      (node (ref "10UH") (pin "1") (pinfunction "1_1") (pintype "passive"))
      (node (ref "C10") (pin "2") (pinfunction "2_2") (pintype "passive"))
      (node (ref "C21") (pin "1") (pinfunction "1_1") (pintype "passive"))
      (node (ref "C27") (pin "2") (pinfunction "2_2") (pintype "passive"))
      (node (ref "C4") (pin "2") (pinfunction "2_2") (pintype "passive"))
      (node (ref "C_IC3") (pin "2") (pinfunction "2_2") (pintype "passive"))
      (node (ref "C_IC5") (pin "2") (pinfunction "2_2") (pintype "passive"))
      (node (ref "C_IC6") (pin "2") (pinfunction "2_2") (pintype "passive"))
      (node (ref "C_IC7") (pin "2") (pinfunction "2_2") (pintype "passive"))
      (node (ref "C_IC9") (pin "2") (pinfunction "2_2") (pintype "passive"))
      (node (ref "FERRITE_BEAD") (pin "1") (pinfunction "1_1") (pintype "passive"))
      (node (ref "IC3") (pin "8") (pinfunction "V+_8") (pintype "power_in"))
      (node (ref "IC5") (pin "8") (pinfunction "V+_8") (pintype "power_in"))
      (node (ref "IC6") (pin "8") (pinfunction "V+_8") (pintype "power_in"))
      (node (ref "IC7") (pin "8") (pinfunction "V+_8") (pintype "power_in"))
      (node (ref "IC9") (pin "8") (pinfunction "V+_8") (pintype "power_in"))
      (node (ref "R13") (pin "1") (pinfunction "1_1") (pintype "passive"))
      (node (ref "R14") (pin "2") (pinfunction "2_2") (pintype "passive"))
      (node (ref "R24") (pin "1") (pinfunction "1_1") (pintype "passive"))
      (node (ref "R6") (pin "1") (pinfunction "1_1") (pintype "passive"))
      (node (ref "R79") (pin "1") (pinfunction "1_1") (pintype "passive"))
      (node (ref "R8") (pin "2") (pinfunction "2_2") (pintype "passive"))
      (node (ref "R80") (pin "1") (pinfunction "1_1") (pintype "passive"))
      (node (ref "R81") (pin "1") (pinfunction "1_1") (pintype "passive"))
      (node (ref "U$1") (pin "11") (pinfunction "11_11") (pintype "power_in"))
      (node (ref "U$19") (pin "3") (pinfunction "VIN_3") (pintype "bidirectional"))
      (node (ref "U$2") (pin "3") (pinfunction "VCC_3") (pintype "bidirectional"))
      (node (ref "U$2") (pin "4") (pinfunction "IN+_4") (pintype "bidirectional"))
      (node (ref "U$3") (pin "3") (pinfunction "VCC_3") (pintype "bidirectional"))
      (node (ref "U$3") (pin "5") (pinfunction "IN-_5") (pintype "bidirectional"))
      (node (ref "U$4") (pin "3") (pinfunction "VIN_3") (pintype "bidirectional"))
      (node (ref "U$5") (pin "3") (pinfunction "FB_3") (pintype "bidirectional"))
      (node (ref "U$5") (pin "4") (pinfunction "VOS_4") (pintype "bidirectional"))
      (node (ref "U$6") (pin "2") (pinfunction "C_2") (pintype "passive"))
      (node (ref "U$7") (pin "2") (pinfunction "C_2") (pintype "passive"))
      (node (ref "U$8") (pin "A") (pinfunction "A_A") (pintype "passive"))
    )
    (net (code "75") (name "unconnected-(U$1-Pad3)") (class "Default")
      (node (ref "U$1") (pin "3") (pinfunction "3_3") (pintype "bidirectional"))
    )
    (net (code "76") (name "unconnected-(U$1-Pad4)") (class "Default")
      (node (ref "U$1") (pin "4") (pinfunction "4_4") (pintype "bidirectional"))
    )
    (net (code "77") (name "unconnected-(U$1-Pad7)") (class "Default")
      (node (ref "U$1") (pin "7") (pinfunction "7_7") (pintype "bidirectional"))
    )
    (net (code "78") (name "unconnected-(U$1-Pad8)") (class "Default")
      (node (ref "U$1") (pin "8") (pinfunction "8_8") (pintype "bidirectional"))
    )
    (net (code "79") (name "unconnected-(U$1-Pad9)") (class "Default")
      (node (ref "U$1") (pin "9") (pinfunction "9_9") (pintype "bidirectional"))
    )
    (net (code "80") (name "unconnected-(U$1-Pad10)") (class "Default")
      (node (ref "U$1") (pin "10") (pinfunction "10_10") (pintype "bidirectional"))
    )
    (net (code "81") (name "unconnected-(U$1-Pad15)") (class "Default")
      (node (ref "U$1") (pin "15") (pinfunction "15_15") (pintype "bidirectional"))
    )
    (net (code "82") (name "unconnected-(U$1-Pad16)") (class "Default")
      (node (ref "U$1") (pin "16") (pinfunction "16_16") (pintype "bidirectional"))
    )
    (net (code "83") (name "unconnected-(U$1-Pad17)") (class "Default")
      (node (ref "U$1") (pin "17") (pinfunction "17_17") (pintype "bidirectional"))
    )
    (net (code "84") (name "unconnected-(U$1-Pad21)") (class "Default")
      (node (ref "U$1") (pin "21") (pinfunction "21_21") (pintype "bidirectional"))
    )
    (net (code "85") (name "unconnected-(U$1-Pad22)") (class "Default")
      (node (ref "U$1") (pin "22") (pinfunction "22_22") (pintype "bidirectional"))
    )
    (net (code "86") (name "unconnected-(U$1-Pad23)") (class "Default")
      (node (ref "U$1") (pin "23") (pinfunction "23_23") (pintype "bidirectional"))
    )
    (net (code "87") (name "unconnected-(U$1-Pad24)") (class "Default")
      (node (ref "U$1") (pin "24") (pinfunction "24_24") (pintype "bidirectional"))
    )
    (net (code "88") (name "unconnected-(U$1-Pad25)") (class "Default")
      (node (ref "U$1") (pin "25") (pinfunction "25_25") (pintype "bidirectional"))
    )
    (net (code "89") (name "unconnected-(U$1-Pad26)") (class "Default")
      (node (ref "U$1") (pin "26") (pinfunction "26_26") (pintype "bidirectional"))
    )
    (net (code "90") (name "unconnected-(U$1-Pad27)") (class "Default")
      (node (ref "U$1") (pin "27") (pinfunction "27_27") (pintype "bidirectional"))
    )
    (net (code "91") (name "unconnected-(U$1-Pad28)") (class "Default")
      (node (ref "U$1") (pin "28") (pinfunction "28_28") (pintype "bidirectional"))
    )
    (net (code "92") (name "unconnected-(U$1-Pad30)") (class "Default")
      (node (ref "U$1") (pin "30") (pinfunction "30_30") (pintype "bidirectional"))
    )
    (net (code "93") (name "unconnected-(U$1-Pad37)") (class "Default")
      (node (ref "U$1") (pin "37") (pinfunction "37_37") (pintype "bidirectional"))
    )
    (net (code "94") (name "unconnected-(U$1-Pad38)") (class "Default")
      (node (ref "U$1") (pin "38") (pinfunction "38_38") (pintype "bidirectional"))
    )
    (net (code "95") (name "unconnected-(U$1-Pad39)") (class "Default")
      (node (ref "U$1") (pin "39") (pinfunction "39_39") (pintype "bidirectional"))
    )
    (net (code "96") (name "unconnected-(U$1-Pad40)") (class "Default")
      (node (ref "U$1") (pin "40") (pinfunction "40_40") (pintype "bidirectional"))
    )
    (net (code "97") (name "unconnected-(U$1-Pad41)") (class "Default")
      (node (ref "U$1") (pin "41") (pinfunction "41_41") (pintype "bidirectional"))
    )
    (net (code "98") (name "unconnected-(U$1-Pad42)") (class "Default")
      (node (ref "U$1") (pin "42") (pinfunction "42_42") (pintype "bidirectional"))
    )
    (net (code "99") (name "unconnected-(U$1-Pad43)") (class "Default")
      (node (ref "U$1") (pin "43") (pinfunction "43_43") (pintype "bidirectional"))
    )
    (net (code "100") (name "unconnected-(U$1-Pad44)") (class "Default")
      (node (ref "U$1") (pin "44") (pinfunction "44_44") (pintype "bidirectional"))
    )
    (net (code "101") (name "unconnected-(U$1-Pad48)") (class "Default")
      (node (ref "U$1") (pin "48") (pinfunction "48_48") (pintype "bidirectional"))
    )
    (net (code "102") (name "unconnected-(U$1-Pad51)") (class "Default")
      (node (ref "U$1") (pin "51") (pinfunction "51_51") (pintype "bidirectional"))
    )
    (net (code "103") (name "unconnected-(U$1-Pad52)") (class "Default")
      (node (ref "U$1") (pin "52") (pinfunction "52_52") (pintype "bidirectional"))
    )
    (net (code "104") (name "unconnected-(U$1-Pad53)") (class "Default")
      (node (ref "U$1") (pin "53") (pinfunction "53_53") (pintype "bidirectional"))
    )
    (net (code "105") (name "unconnected-(U$1-Pad54)") (class "Default")
      (node (ref "U$1") (pin "54") (pinfunction "54_54") (pintype "bidirectional"))
    )
    (net (code "106") (name "unconnected-(U$1-Pad55)") (class "Default")
      (node (ref "U$1") (pin "55") (pinfunction "55_55") (pintype "bidirectional"))
    )
    (net (code "107") (name "unconnected-(U$1-Pad56)") (class "Default")
      (node (ref "U$1") (pin "56") (pinfunction "56_56") (pintype "bidirectional"))
    )
    (net (code "108") (name "unconnected-(U$1-Pad57)") (class "Default")
      (node (ref "U$1") (pin "57") (pinfunction "57_57") (pintype "bidirectional"))
    )
    (net (code "109") (name "unconnected-(U$1-Pad58)") (class "Default")
      (node (ref "U$1") (pin "58") (pinfunction "58_58") (pintype "bidirectional"))
    )
    (net (code "110") (name "unconnected-(U$1-Pad59)") (class "Default")
      (node (ref "U$1") (pin "59") (pinfunction "59_59") (pintype "bidirectional"))
    )
    (net (code "111") (name "unconnected-(U$1-Pad60)") (class "Default")
      (node (ref "U$1") (pin "60") (pinfunction "60_60") (pintype "bidirectional"))
    )
    (net (code "112") (name "unconnected-(U$1-Pad62)") (class "Default")
      (node (ref "U$1") (pin "62") (pinfunction "62_62") (pintype "bidirectional"))
    )
    (net (code "113") (name "unconnected-(U$1-Pad64)") (class "Default")
      (node (ref "U$1") (pin "64") (pinfunction "64_64") (pintype "bidirectional"))
    )
    (net (code "114") (name "unconnected-(U$1-Pad69)") (class "Default")
      (node (ref "U$1") (pin "69") (pinfunction "69_69") (pintype "bidirectional"))
    )
    (net (code "115") (name "unconnected-(U$1-Pad70)") (class "Default")
      (node (ref "U$1") (pin "70") (pinfunction "70_70") (pintype "bidirectional"))
    )
    (net (code "116") (name "unconnected-(U$1-Pad72)") (class "Default")
      (node (ref "U$1") (pin "72") (pinfunction "72_72") (pintype "bidirectional"))
    )
    (net (code "117") (name "unconnected-(U$1-Pad73)") (class "Default")
      (node (ref "U$1") (pin "73") (pinfunction "73_73") (pintype "bidirectional"))
    )
    (net (code "118") (name "unconnected-(U$1-Pad74)") (class "Default")
      (node (ref "U$1") (pin "74") (pinfunction "74_74") (pintype "bidirectional"))
    )
    (net (code "119") (name "unconnected-(U$1-Pad75)") (class "Default")
      (node (ref "U$1") (pin "75") (pinfunction "75_75") (pintype "bidirectional"))
    )
    (net (code "120") (name "unconnected-(U$4-PG-Pad6)") (class "Default")
      (node (ref "U$4") (pin "6") (pinfunction "PG_6") (pintype "bidirectional"))
    )
    (net (code "121") (name "unconnected-(U$16-OC-Pad5)") (class "Default")
      (node (ref "U$16") (pin "5") (pinfunction "OC_5") (pintype "bidirectional"))
    )
    (net (code "122") (name "unconnected-(U$17-OC-Pad5)") (class "Default")
      (node (ref "U$17") (pin "5") (pinfunction "OC_5") (pintype "bidirectional"))
    )
    (net (code "123") (name "unconnected-(U$18-OC-Pad5)") (class "Default")
      (node (ref "U$18") (pin "5") (pinfunction "OC_5") (pintype "bidirectional"))
    )
    (net (code "124") (name "unconnected-(U$19-NC1-Pad1)") (class "Default")
      (node (ref "U$19") (pin "1") (pinfunction "NC1_1") (pintype "bidirectional"))
    )
    (net (code "125") (name "unconnected-(U$19-NC2-Pad5)") (class "Default")
      (node (ref "U$19") (pin "5") (pinfunction "NC2_5") (pintype "bidirectional"))
    )
    (net (code "126") (name "unconnected-(U$19-NC3-Pad6)") (class "Default")
      (node (ref "U$19") (pin "6") (pinfunction "NC3_6") (pintype "bidirectional"))
    )
  )
)
